# working.net
KiCad netlist of a schematic drawn in EAGLE
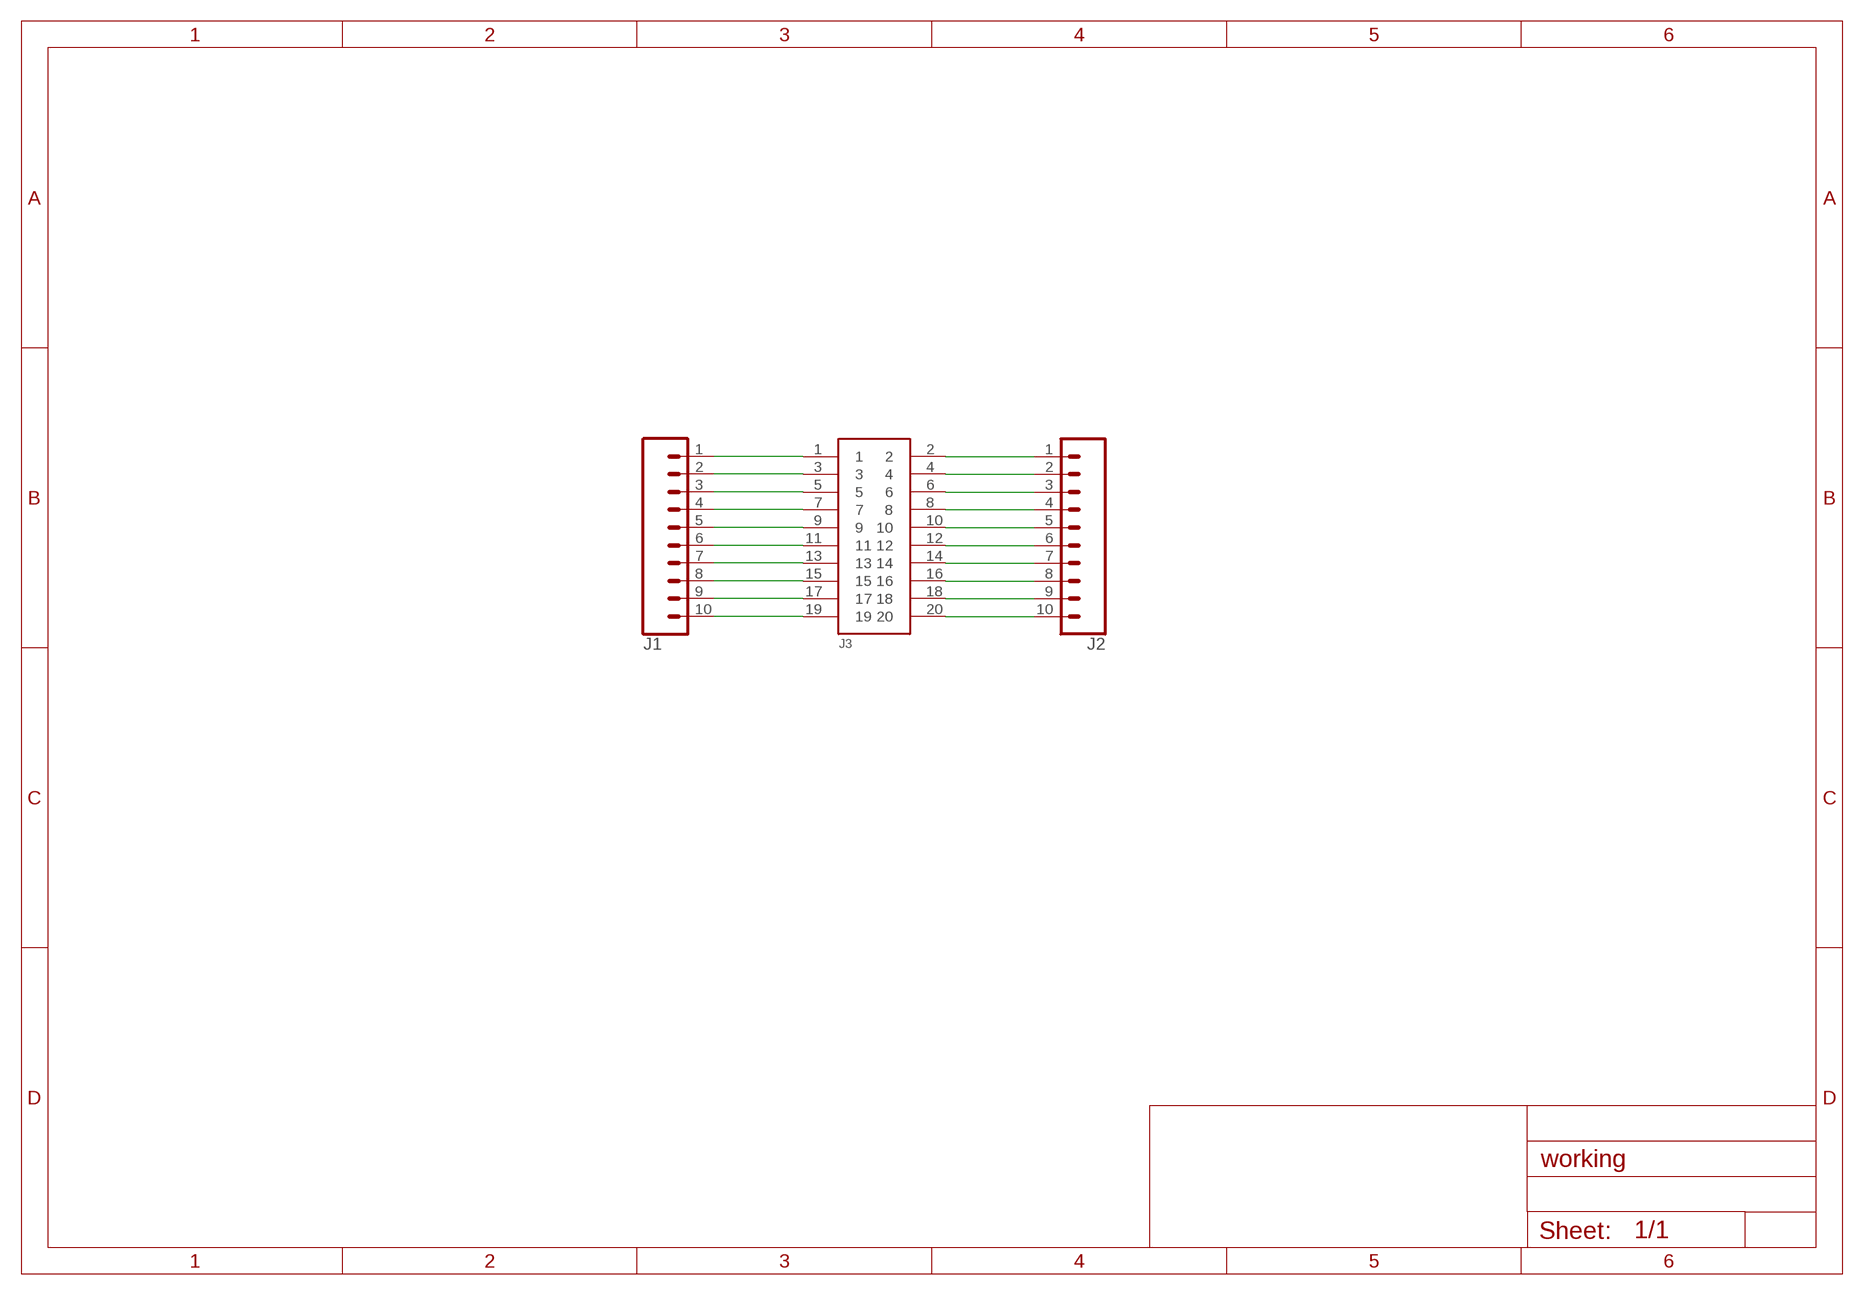
[diagram p0: schematic, sheet 1]

(export (version "E")
  (design (tool "Eeschema 10.0.6"))
  (components
    (comp (ref "J1")
      (value "CONN_10\"")
      (footprint "eagle-import:1X10")
      (libsource (lib "eagle-import") (part "CONN_10{dblquote}"))
    )
    (comp (ref "J2")
      (value "CONN_10\"")
      (footprint "eagle-import:1X10")
      (libsource (lib "eagle-import") (part "CONN_10{dblquote}"))
    )
    (comp (ref "J3")
      (value "ST4-10-X.XX-X-D")
      (footprint "eagle-import:ST4-10-X.XX-X-D")
      (libsource (lib "eagle-import") (part "ST4-10-X.XX-X-D"))
    )
  )
  (nets
    (net (code "1") (name "Net-(J1-Pad1)") (class "Default")
      (node (ref "J1") (pin "1") (pinfunction "1_1") (pintype "passive"))
      (node (ref "J3") (pin "1") (pinfunction "1_1") (pintype "bidirectional"))
    )
    (net (code "2") (name "Net-(J1-Pad2)") (class "Default")
      (node (ref "J1") (pin "2") (pinfunction "2_2") (pintype "passive"))
      (node (ref "J3") (pin "3") (pinfunction "3_3") (pintype "bidirectional"))
    )
    (net (code "3") (name "Net-(J1-Pad3)") (class "Default")
      (node (ref "J1") (pin "3") (pinfunction "3_3") (pintype "passive"))
      (node (ref "J3") (pin "5") (pinfunction "5_5") (pintype "bidirectional"))
    )
    (net (code "4") (name "Net-(J1-Pad4)") (class "Default")
      (node (ref "J1") (pin "4") (pinfunction "4_4") (pintype "passive"))
      (node (ref "J3") (pin "7") (pinfunction "7_7") (pintype "bidirectional"))
    )
    (net (code "5") (name "Net-(J1-Pad5)") (class "Default")
      (node (ref "J1") (pin "5") (pinfunction "5_5") (pintype "passive"))
      (node (ref "J3") (pin "9") (pinfunction "9_9") (pintype "bidirectional"))
    )
    (net (code "6") (name "Net-(J1-Pad6)") (class "Default")
      (node (ref "J1") (pin "6") (pinfunction "6_6") (pintype "passive"))
      (node (ref "J3") (pin "11") (pinfunction "11_11") (pintype "bidirectional"))
    )
    (net (code "7") (name "Net-(J1-Pad7)") (class "Default")
      (node (ref "J1") (pin "7") (pinfunction "7_7") (pintype "passive"))
      (node (ref "J3") (pin "13") (pinfunction "13_13") (pintype "bidirectional"))
    )
    (net (code "8") (name "Net-(J1-Pad8)") (class "Default")
      (node (ref "J1") (pin "8") (pinfunction "8_8") (pintype "passive"))
      (node (ref "J3") (pin "15") (pinfunction "15_15") (pintype "bidirectional"))
    )
    (net (code "9") (name "Net-(J1-Pad9)") (class "Default")
      (node (ref "J1") (pin "9") (pinfunction "9_9") (pintype "passive"))
      (node (ref "J3") (pin "17") (pinfunction "17_17") (pintype "bidirectional"))
    )
    (net (code "10") (name "Net-(J1-Pad10)") (class "Default")
      (node (ref "J1") (pin "10") (pinfunction "10_10") (pintype "passive"))
      (node (ref "J3") (pin "19") (pinfunction "19_19") (pintype "bidirectional"))
    )
    (net (code "11") (name "Net-(J2-Pad1)") (class "Default")
      (node (ref "J2") (pin "1") (pinfunction "1_1") (pintype "passive"))
      (node (ref "J3") (pin "2") (pinfunction "2_2") (pintype "bidirectional"))
    )
    (net (code "12") (name "Net-(J2-Pad2)") (class "Default")
      (node (ref "J2") (pin "2") (pinfunction "2_2") (pintype "passive"))
      (node (ref "J3") (pin "4") (pinfunction "4_4") (pintype "bidirectional"))
    )
    (net (code "13") (name "Net-(J2-Pad3)") (class "Default")
      (node (ref "J2") (pin "3") (pinfunction "3_3") (pintype "passive"))
      (node (ref "J3") (pin "6") (pinfunction "6_6") (pintype "bidirectional"))
    )
    (net (code "14") (name "Net-(J2-Pad4)") (class "Default")
      (node (ref "J2") (pin "4") (pinfunction "4_4") (pintype "passive"))
      (node (ref "J3") (pin "8") (pinfunction "8_8") (pintype "bidirectional"))
    )
    (net (code "15") (name "Net-(J2-Pad5)") (class "Default")
      (node (ref "J2") (pin "5") (pinfunction "5_5") (pintype "passive"))
      (node (ref "J3") (pin "10") (pinfunction "10_10") (pintype "bidirectional"))
    )
    (net (code "16") (name "Net-(J2-Pad6)") (class "Default")
      (node (ref "J2") (pin "6") (pinfunction "6_6") (pintype "passive"))
      (node (ref "J3") (pin "12") (pinfunction "12_12") (pintype "bidirectional"))
    )
    (net (code "17") (name "Net-(J2-Pad7)") (class "Default")
      (node (ref "J2") (pin "7") (pinfunction "7_7") (pintype "passive"))
      (node (ref "J3") (pin "14") (pinfunction "14_14") (pintype "bidirectional"))
    )
    (net (code "18") (name "Net-(J2-Pad8)") (class "Default")
      (node (ref "J2") (pin "8") (pinfunction "8_8") (pintype "passive"))
      (node (ref "J3") (pin "16") (pinfunction "16_16") (pintype "bidirectional"))
    )
    (net (code "19") (name "Net-(J2-Pad9)") (class "Default")
      (node (ref "J2") (pin "9") (pinfunction "9_9") (pintype "passive"))
      (node (ref "J3") (pin "18") (pinfunction "18_18") (pintype "bidirectional"))
    )
    (net (code "20") (name "Net-(J2-Pad10)") (class "Default")
      (node (ref "J2") (pin "10") (pinfunction "10_10") (pintype "passive"))
      (node (ref "J3") (pin "20") (pinfunction "20_20") (pintype "bidirectional"))
    )
  )
)
